# garage_door_opener_v2_2015_07_16.net
KiCad netlist of a schematic drawn in EAGLE
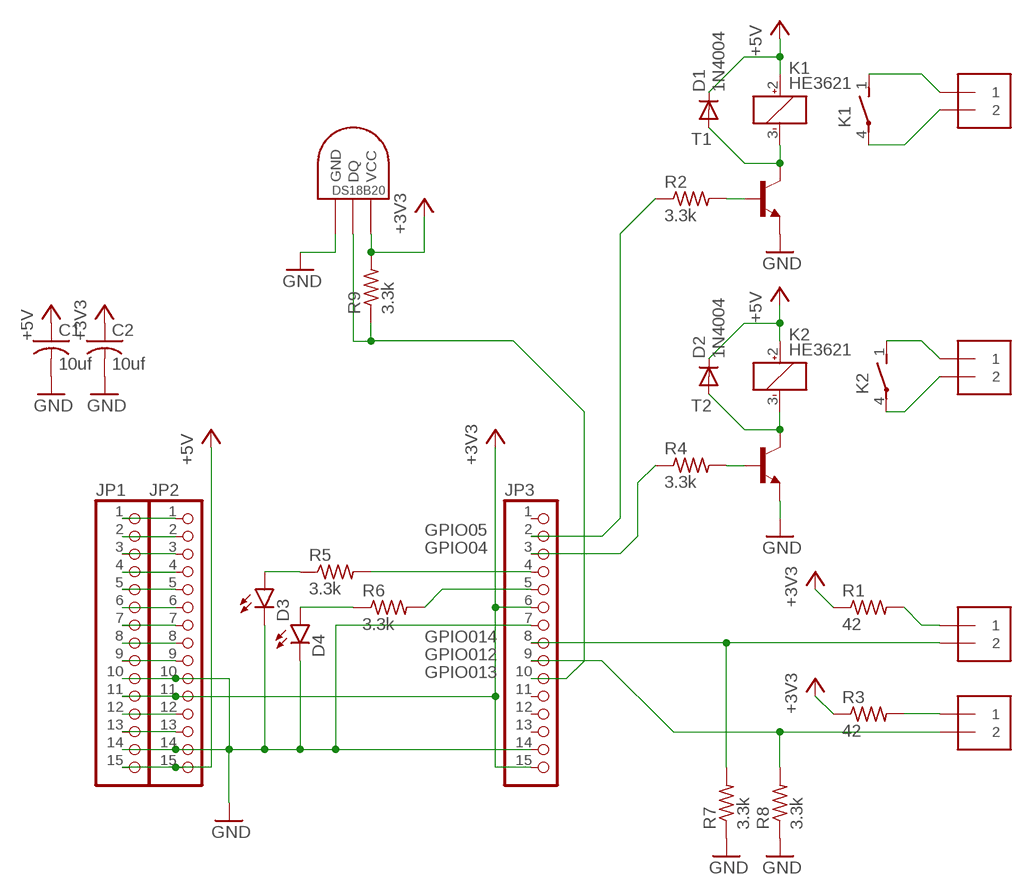
[diagram p0: schematic, sheet 1]

(export (version "E")
  (design (tool "Eeschema 10.0.6"))
  (components
    (comp (ref "C1")
      (value "10uf")
      (footprint "eagle-import:C0603")
      (libsource (lib "eagle-import") (part "C-USC0603"))
    )
    (comp (ref "C2")
      (value "10uf")
      (footprint "eagle-import:C0603")
      (libsource (lib "eagle-import") (part "C-USC0603"))
    )
    (comp (ref "D1")
      (value "1N4004")
      (footprint "eagle-import:DO214BA")
      (libsource (lib "eagle-import") (part "DIODE-DO214BA"))
    )
    (comp (ref "D2")
      (value "1N4004")
      (footprint "eagle-import:DO214BA")
      (libsource (lib "eagle-import") (part "DIODE-DO214BA"))
    )
    (comp (ref "D3")
      (value "LED0603")
      (footprint "eagle-import:LED-0603")
      (libsource (lib "eagle-import") (part "LED0603"))
    )
    (comp (ref "D4")
      (value "LED0603")
      (footprint "eagle-import:LED-0603")
      (libsource (lib "eagle-import") (part "LED0603"))
    )
    (comp (ref "DS18B20")
      (value "DS18B20TO92")
      (footprint "eagle-import:DS1820")
      (libsource (lib "eagle-import") (part "DS1820TO92"))
    )
    (comp (ref "JP1")
      (value "PINHD-1X15")
      (footprint "eagle-import:1X15")
      (libsource (lib "eagle-import") (part "PINHD-1X15"))
    )
    (comp (ref "JP2")
      (value "PINHD-1X15")
      (footprint "eagle-import:1X15")
      (libsource (lib "eagle-import") (part "PINHD-1X15"))
    )
    (comp (ref "JP3")
      (value "PINHD-1X15")
      (footprint "eagle-import:1X15")
      (libsource (lib "eagle-import") (part "PINHD-1X15"))
    )
    (comp (ref "K1")
      (value "HE3621")
      (footprint "eagle-import:HE3621")
      (fields
        (field (name "MF") "HAMLIN")
        (field (name "MPN") "HE3621A2410")
        (field (name "MPN_1") "HE3621A0510")
      )
      (libsource (lib "eagle-import") (part "HE3621"))
    )
    (comp (ref "K2")
      (value "HE3621")
      (footprint "eagle-import:HE3621")
      (fields
        (field (name "MF") "HAMLIN")
        (field (name "MPN") "HE3621A2410")
        (field (name "MPN_1") "HE3621A0510")
      )
      (libsource (lib "eagle-import") (part "HE3621"))
    )
    (comp (ref "OPEN1")
      (value "1X2-3.5MM")
      (footprint "eagle-import:1X2-3.5MM")
      (fields (field (name "MPN") "OSTTE020161"))
      (libsource (lib "eagle-import") (part "1X2-3.5MM"))
    )
    (comp (ref "OPEN2")
      (value "1X2-3.5MM")
      (footprint "eagle-import:1X2-3.5MM")
      (fields (field (name "MPN") "OSTTE020161"))
      (libsource (lib "eagle-import") (part "1X2-3.5MM"))
    )
    (comp (ref "R1")
      (value "42")
      (footprint "eagle-import:R0603")
      (libsource (lib "eagle-import") (part "R-US_R0603"))
    )
    (comp (ref "R2")
      (value "3.3k")
      (footprint "eagle-import:R0603")
      (libsource (lib "eagle-import") (part "R-US_R0603"))
    )
    (comp (ref "R3")
      (value "42")
      (footprint "eagle-import:R0603")
      (libsource (lib "eagle-import") (part "R-US_R0603"))
    )
    (comp (ref "R4")
      (value "3.3k")
      (footprint "eagle-import:R0603")
      (libsource (lib "eagle-import") (part "R-US_R0603"))
    )
    (comp (ref "R5")
      (value "3.3k")
      (footprint "eagle-import:R0603")
      (libsource (lib "eagle-import") (part "R-US_R0603"))
    )
    (comp (ref "R6")
      (value "3.3k")
      (footprint "eagle-import:R0603")
      (libsource (lib "eagle-import") (part "R-US_R0603"))
    )
    (comp (ref "R7")
      (value "3.3k")
      (footprint "eagle-import:R0603")
      (libsource (lib "eagle-import") (part "R-US_R0603"))
    )
    (comp (ref "R8")
      (value "3.3k")
      (footprint "eagle-import:R0603")
      (libsource (lib "eagle-import") (part "R-US_R0603"))
    )
    (comp (ref "R9")
      (value "3.3k")
      (footprint "eagle-import:R0603")
      (libsource (lib "eagle-import") (part "R-US_R0603"))
    )
    (comp (ref "SENS1")
      (value "1X2-3.5MM")
      (footprint "eagle-import:1X2-3.5MM")
      (fields (field (name "MPN") "OSTTE020161"))
      (libsource (lib "eagle-import") (part "1X2-3.5MM"))
    )
    (comp (ref "SENS2")
      (value "1X2-3.5MM")
      (footprint "eagle-import:1X2-3.5MM")
      (fields (field (name "MPN") "OSTTE020161"))
      (libsource (lib "eagle-import") (part "1X2-3.5MM"))
    )
    (comp (ref "T1")
      (value "MMBT3904LT1-NPN-SOT23-BEC")
      (footprint "eagle-import:SOT23-BEC")
      (fields (field (name "MPN") "MMBT2222A"))
      (libsource (lib "eagle-import") (part "-NPN-SOT23-BECMMBT3904LT1"))
    )
    (comp (ref "T2")
      (value "MMBT3904LT1-NPN-SOT23-BEC")
      (footprint "eagle-import:SOT23-BEC")
      (fields (field (name "MPN") "MMBT2222A"))
      (libsource (lib "eagle-import") (part "-NPN-SOT23-BECMMBT3904LT1"))
    )
  )
  (nets
    (net (code "1") (name "+3V3") (class "Default")
      (node (ref "C2") (pin "1") (pinfunction "1_1") (pintype "passive"))
      (node (ref "DS18B20") (pin "VDD") (pinfunction "VCC_VDD") (pintype "power_in"))
      (node (ref "JP1") (pin "11") (pinfunction "11_11") (pintype "passive"))
      (node (ref "JP2") (pin "11") (pinfunction "11_11") (pintype "passive"))
      (node (ref "JP3") (pin "15") (pinfunction "15_15") (pintype "passive"))
      (node (ref "JP3") (pin "6") (pinfunction "6_6") (pintype "passive"))
      (node (ref "R1") (pin "1") (pinfunction "1_1") (pintype "passive"))
      (node (ref "R3") (pin "1") (pinfunction "1_1") (pintype "passive"))
      (node (ref "R9") (pin "2") (pinfunction "2_2") (pintype "passive"))
    )
    (net (code "2") (name "+5V") (class "Default")
      (node (ref "C1") (pin "1") (pinfunction "1_1") (pintype "passive"))
      (node (ref "D1") (pin "C") (pinfunction "C_C") (pintype "passive"))
      (node (ref "D2") (pin "C") (pinfunction "C_C") (pintype "passive"))
      (node (ref "JP1") (pin "15") (pinfunction "15_15") (pintype "passive"))
      (node (ref "JP2") (pin "15") (pinfunction "15_15") (pintype "passive"))
      (node (ref "K1") (pin "2") (pinfunction "+_2") (pintype "passive"))
      (node (ref "K2") (pin "2") (pinfunction "+_2") (pintype "passive"))
    )
    (net (code "3") (name "GND") (class "Default")
      (node (ref "C1") (pin "2") (pinfunction "2_2") (pintype "passive"))
      (node (ref "C2") (pin "2") (pinfunction "2_2") (pintype "passive"))
      (node (ref "D3") (pin "C") (pinfunction "C_C") (pintype "passive"))
      (node (ref "D4") (pin "C") (pinfunction "C_C") (pintype "passive"))
      (node (ref "DS18B20") (pin "GND") (pinfunction "GND_GND") (pintype "power_in"))
      (node (ref "JP1") (pin "10") (pinfunction "10_10") (pintype "passive"))
      (node (ref "JP1") (pin "14") (pinfunction "14_14") (pintype "passive"))
      (node (ref "JP2") (pin "10") (pinfunction "10_10") (pintype "passive"))
      (node (ref "JP2") (pin "14") (pinfunction "14_14") (pintype "passive"))
      (node (ref "JP3") (pin "14") (pinfunction "14_14") (pintype "passive"))
      (node (ref "JP3") (pin "7") (pinfunction "7_7") (pintype "passive"))
      (node (ref "R7") (pin "1") (pinfunction "1_1") (pintype "passive"))
      (node (ref "R8") (pin "1") (pinfunction "1_1") (pintype "passive"))
      (node (ref "T1") (pin "E") (pinfunction "E_E") (pintype "passive"))
      (node (ref "T2") (pin "E") (pinfunction "E_E") (pintype "passive"))
    )
    (net (code "4") (name "Net-(D3-PadA)") (class "Default")
      (node (ref "D3") (pin "A") (pinfunction "A_A") (pintype "passive"))
      (node (ref "R5") (pin "1") (pinfunction "1_1") (pintype "passive"))
    )
    (net (code "5") (name "Net-(D4-PadA)") (class "Default")
      (node (ref "D4") (pin "A") (pinfunction "A_A") (pintype "passive"))
      (node (ref "R6") (pin "1") (pinfunction "1_1") (pintype "passive"))
    )
    (net (code "6") (name "Net-(DS18B20-PadDQ)") (class "Default")
      (node (ref "DS18B20") (pin "DQ") (pinfunction "DQ_DQ") (pintype "bidirectional"))
      (node (ref "JP3") (pin "10") (pinfunction "10_10") (pintype "passive"))
      (node (ref "R9") (pin "1") (pinfunction "1_1") (pintype "passive"))
    )
    (net (code "7") (name "Net-(JP1-Pad1)") (class "Default")
      (node (ref "JP1") (pin "1") (pinfunction "1_1") (pintype "passive"))
      (node (ref "JP2") (pin "1") (pinfunction "1_1") (pintype "passive"))
    )
    (net (code "8") (name "Net-(JP1-Pad2)") (class "Default")
      (node (ref "JP1") (pin "2") (pinfunction "2_2") (pintype "passive"))
      (node (ref "JP2") (pin "2") (pinfunction "2_2") (pintype "passive"))
    )
    (net (code "9") (name "Net-(JP1-Pad3)") (class "Default")
      (node (ref "JP1") (pin "3") (pinfunction "3_3") (pintype "passive"))
      (node (ref "JP2") (pin "3") (pinfunction "3_3") (pintype "passive"))
    )
    (net (code "10") (name "Net-(JP1-Pad4)") (class "Default")
      (node (ref "JP1") (pin "4") (pinfunction "4_4") (pintype "passive"))
      (node (ref "JP2") (pin "4") (pinfunction "4_4") (pintype "passive"))
    )
    (net (code "11") (name "Net-(JP1-Pad5)") (class "Default")
      (node (ref "JP1") (pin "5") (pinfunction "5_5") (pintype "passive"))
      (node (ref "JP2") (pin "5") (pinfunction "5_5") (pintype "passive"))
    )
    (net (code "12") (name "Net-(JP1-Pad6)") (class "Default")
      (node (ref "JP1") (pin "6") (pinfunction "6_6") (pintype "passive"))
      (node (ref "JP2") (pin "6") (pinfunction "6_6") (pintype "passive"))
    )
    (net (code "13") (name "Net-(JP1-Pad7)") (class "Default")
      (node (ref "JP1") (pin "7") (pinfunction "7_7") (pintype "passive"))
      (node (ref "JP2") (pin "7") (pinfunction "7_7") (pintype "passive"))
    )
    (net (code "14") (name "Net-(JP1-Pad8)") (class "Default")
      (node (ref "JP1") (pin "8") (pinfunction "8_8") (pintype "passive"))
      (node (ref "JP2") (pin "8") (pinfunction "8_8") (pintype "passive"))
    )
    (net (code "15") (name "Net-(JP1-Pad9)") (class "Default")
      (node (ref "JP1") (pin "9") (pinfunction "9_9") (pintype "passive"))
      (node (ref "JP2") (pin "9") (pinfunction "9_9") (pintype "passive"))
    )
    (net (code "16") (name "Net-(JP1-Pad12)") (class "Default")
      (node (ref "JP1") (pin "12") (pinfunction "12_12") (pintype "passive"))
      (node (ref "JP2") (pin "12") (pinfunction "12_12") (pintype "passive"))
    )
    (net (code "17") (name "Net-(JP1-Pad13)") (class "Default")
      (node (ref "JP1") (pin "13") (pinfunction "13_13") (pintype "passive"))
      (node (ref "JP2") (pin "13") (pinfunction "13_13") (pintype "passive"))
    )
    (net (code "18") (name "Net-(JP3-Pad2)") (class "Default")
      (node (ref "JP3") (pin "2") (pinfunction "2_2") (pintype "passive"))
      (node (ref "R2") (pin "1") (pinfunction "1_1") (pintype "passive"))
    )
    (net (code "19") (name "Net-(JP3-Pad3)") (class "Default")
      (node (ref "JP3") (pin "3") (pinfunction "3_3") (pintype "passive"))
      (node (ref "R4") (pin "1") (pinfunction "1_1") (pintype "passive"))
    )
    (net (code "20") (name "Net-(JP3-Pad4)") (class "Default")
      (node (ref "JP3") (pin "4") (pinfunction "4_4") (pintype "passive"))
      (node (ref "R5") (pin "2") (pinfunction "2_2") (pintype "passive"))
    )
    (net (code "21") (name "Net-(JP3-Pad5)") (class "Default")
      (node (ref "JP3") (pin "5") (pinfunction "5_5") (pintype "passive"))
      (node (ref "R6") (pin "2") (pinfunction "2_2") (pintype "passive"))
    )
    (net (code "22") (name "Net-(JP3-Pad8)") (class "Default")
      (node (ref "JP3") (pin "8") (pinfunction "8_8") (pintype "passive"))
      (node (ref "R7") (pin "2") (pinfunction "2_2") (pintype "passive"))
      (node (ref "SENS1") (pin "2") (pinfunction "2_2") (pintype "passive"))
    )
    (net (code "23") (name "Net-(JP3-Pad9)") (class "Default")
      (node (ref "JP3") (pin "9") (pinfunction "9_9") (pintype "passive"))
      (node (ref "R8") (pin "2") (pinfunction "2_2") (pintype "passive"))
      (node (ref "SENS2") (pin "2") (pinfunction "2_2") (pintype "passive"))
    )
    (net (code "24") (name "Net-(K1A--)") (class "Default")
      (node (ref "D1") (pin "A") (pinfunction "A_A") (pintype "passive"))
      (node (ref "K1") (pin "3") (pinfunction "-_3") (pintype "passive"))
      (node (ref "T1") (pin "C") (pinfunction "C_C") (pintype "passive"))
    )
    (net (code "25") (name "Net-(K1B-P)") (class "Default")
      (node (ref "K1") (pin "4") (pinfunction "P_4") (pintype "passive"))
      (node (ref "OPEN1") (pin "2") (pinfunction "2_2") (pintype "passive"))
    )
    (net (code "26") (name "Net-(K1B-S)") (class "Default")
      (node (ref "K1") (pin "1") (pinfunction "S_1") (pintype "passive"))
      (node (ref "OPEN1") (pin "1") (pinfunction "1_1") (pintype "passive"))
    )
    (net (code "27") (name "Net-(K2A--)") (class "Default")
      (node (ref "D2") (pin "A") (pinfunction "A_A") (pintype "passive"))
      (node (ref "K2") (pin "3") (pinfunction "-_3") (pintype "passive"))
      (node (ref "T2") (pin "C") (pinfunction "C_C") (pintype "passive"))
    )
    (net (code "28") (name "Net-(K2B-P)") (class "Default")
      (node (ref "K2") (pin "4") (pinfunction "P_4") (pintype "passive"))
      (node (ref "OPEN2") (pin "2") (pinfunction "2_2") (pintype "passive"))
    )
    (net (code "29") (name "Net-(K2B-S)") (class "Default")
      (node (ref "K2") (pin "1") (pinfunction "S_1") (pintype "passive"))
      (node (ref "OPEN2") (pin "1") (pinfunction "1_1") (pintype "passive"))
    )
    (net (code "30") (name "Net-(R1-Pad2)") (class "Default")
      (node (ref "R1") (pin "2") (pinfunction "2_2") (pintype "passive"))
      (node (ref "SENS1") (pin "1") (pinfunction "1_1") (pintype "passive"))
    )
    (net (code "31") (name "Net-(R2-Pad2)") (class "Default")
      (node (ref "R2") (pin "2") (pinfunction "2_2") (pintype "passive"))
      (node (ref "T1") (pin "B") (pinfunction "B_B") (pintype "passive"))
    )
    (net (code "32") (name "Net-(R3-Pad2)") (class "Default")
      (node (ref "R3") (pin "2") (pinfunction "2_2") (pintype "passive"))
      (node (ref "SENS2") (pin "1") (pinfunction "1_1") (pintype "passive"))
    )
    (net (code "33") (name "Net-(R4-Pad2)") (class "Default")
      (node (ref "R4") (pin "2") (pinfunction "2_2") (pintype "passive"))
      (node (ref "T2") (pin "B") (pinfunction "B_B") (pintype "passive"))
    )
    (net (code "34") (name "unconnected-(JP3-Pad1)") (class "Default")
      (node (ref "JP3") (pin "1") (pinfunction "1_1") (pintype "passive"))
    )
    (net (code "35") (name "unconnected-(JP3-Pad11)") (class "Default")
      (node (ref "JP3") (pin "11") (pinfunction "11_11") (pintype "passive"))
    )
    (net (code "36") (name "unconnected-(JP3-Pad12)") (class "Default")
      (node (ref "JP3") (pin "12") (pinfunction "12_12") (pintype "passive"))
    )
    (net (code "37") (name "unconnected-(JP3-Pad13)") (class "Default")
      (node (ref "JP3") (pin "13") (pinfunction "13_13") (pintype "passive"))
    )
  )
)
